# HIDdoorUnlocker.net
KiCad netlist of a schematic drawn in EAGLE
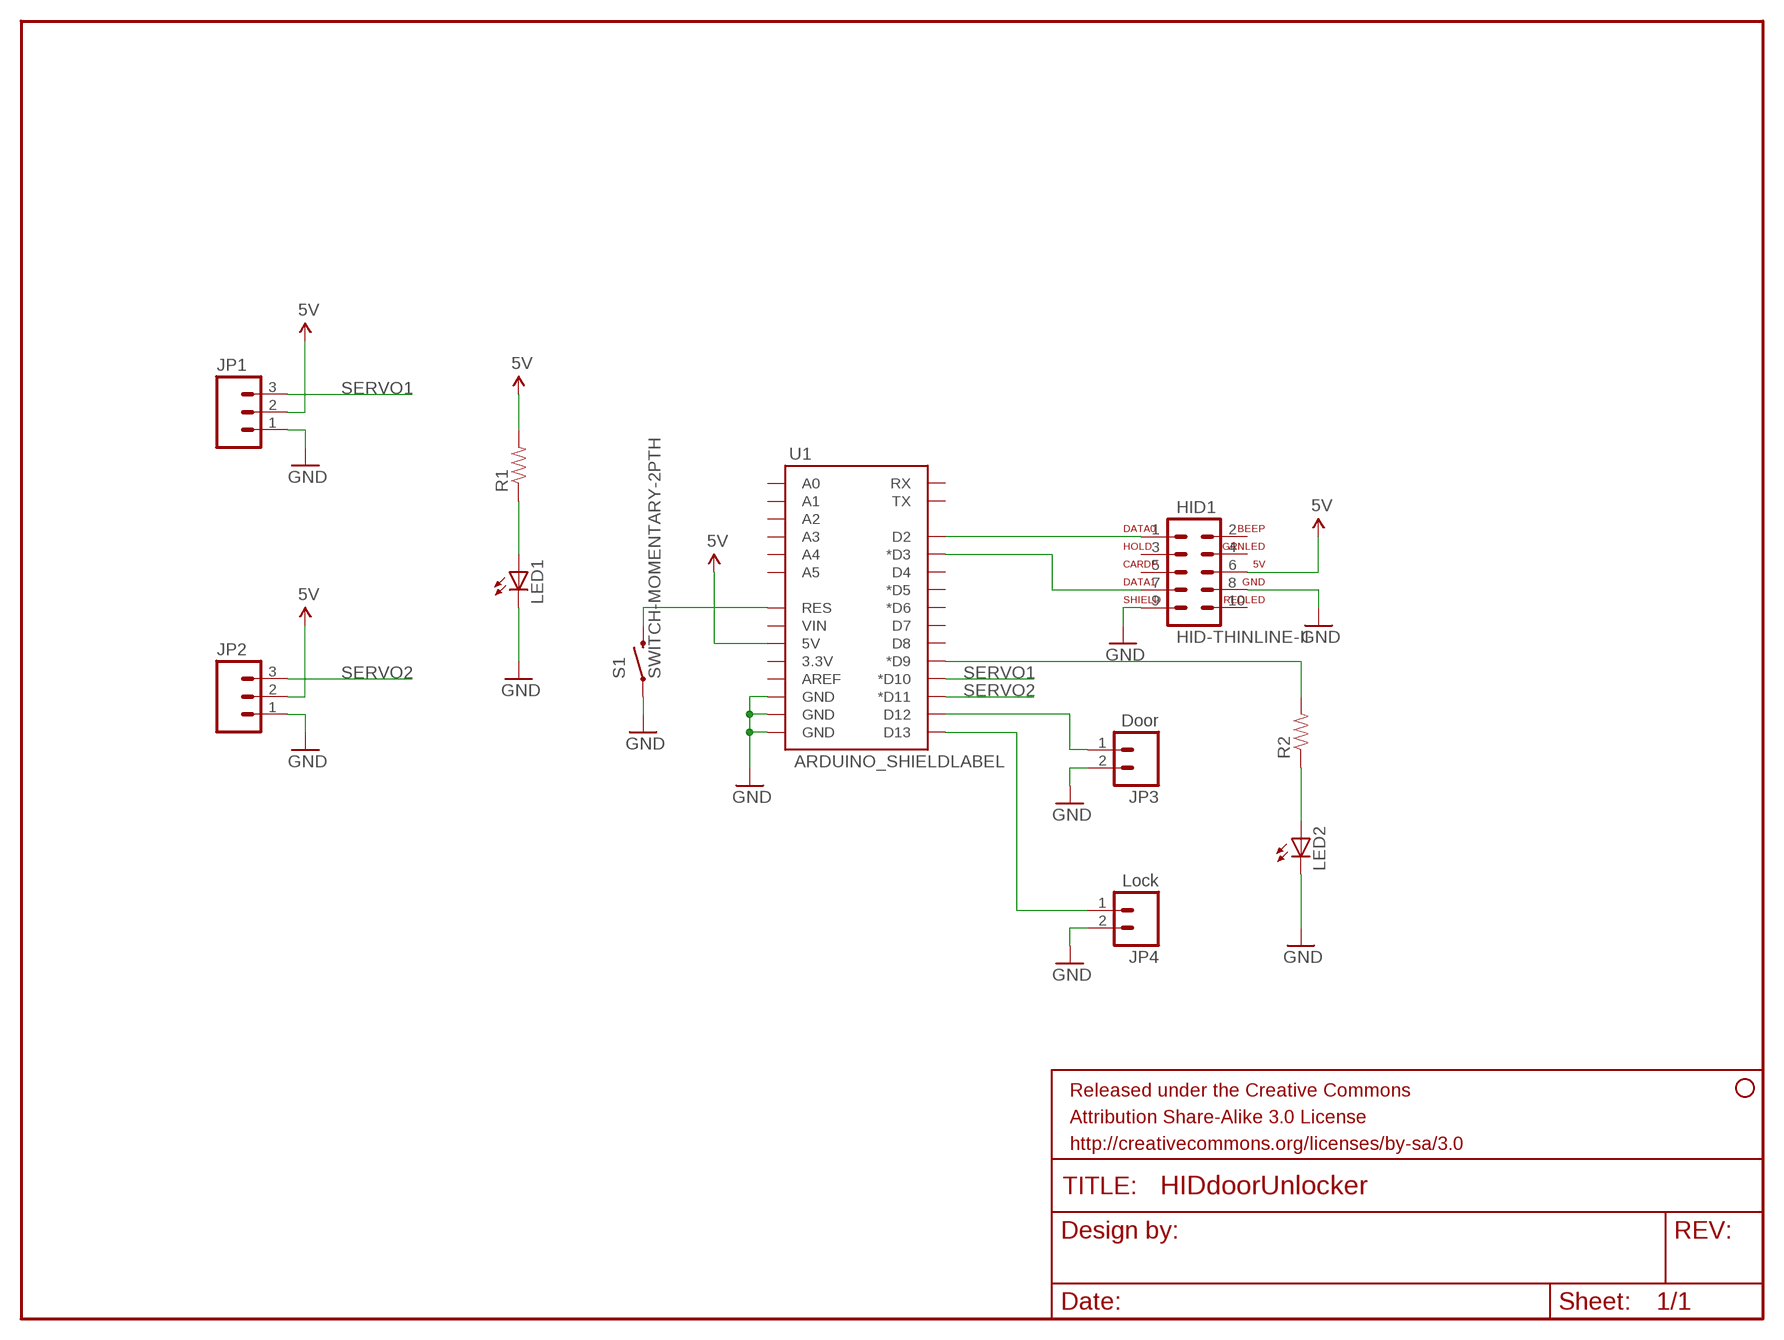
[diagram p0: schematic, sheet 1]

(export (version "E")
  (design (tool "Eeschema 10.0.6"))
  (components
    (comp (ref "FRAME1")
      (value "FRAME-LETTER")
      (footprint "eagle-import:CREATIVE_COMMONS")
      (libsource (lib "eagle-import") (part "FRAME-LETTER"))
    )
    (comp (ref "HID1")
      (value "HID-THINLINE-II")
      (footprint "eagle-import:HID-2X5")
      (libsource (lib "eagle-import") (part "HID-THINLINE-II"))
    )
    (comp (ref "JP1")
      (value "M03PTH")
      (footprint "eagle-import:1X03")
      (libsource (lib "eagle-import") (part "M03PTH"))
    )
    (comp (ref "JP2")
      (value "M03PTH")
      (footprint "eagle-import:1X03")
      (libsource (lib "eagle-import") (part "M03PTH"))
    )
    (comp (ref "JP3")
      (value "Door")
      (footprint "eagle-import:1X02")
      (libsource (lib "eagle-import") (part "M02PTH"))
    )
    (comp (ref "JP4")
      (value "Lock")
      (footprint "eagle-import:1X02")
      (libsource (lib "eagle-import") (part "M02PTH"))
    )
    (comp (ref "LED1")
      (value "LED5MM")
      (footprint "eagle-import:LED5MM")
      (libsource (lib "eagle-import") (part "LED5MM"))
    )
    (comp (ref "LED2")
      (value "LED5MM")
      (footprint "eagle-import:LED5MM")
      (libsource (lib "eagle-import") (part "LED5MM"))
    )
    (comp (ref "R1")
      (value "RESISTORPTH-1/4W")
      (footprint "eagle-import:AXIAL-0.4")
      (libsource (lib "eagle-import") (part "RESISTORPTH-1/4W"))
    )
    (comp (ref "R2")
      (value "RESISTORPTH-1/4W")
      (footprint "eagle-import:AXIAL-0.4")
      (libsource (lib "eagle-import") (part "RESISTORPTH-1/4W"))
    )
    (comp (ref "S1")
      (value "SWITCH-MOMENTARY-2PTH")
      (footprint "eagle-import:TACTILE-PTH")
      (libsource (lib "eagle-import") (part "SWITCH-MOMENTARY-2PTH"))
    )
    (comp (ref "STANDOFF1")
      (value "STAND-OFF")
      (footprint "eagle-import:STAND-OFF")
      (libsource (lib "eagle-import") (part "STAND-OFF"))
    )
    (comp (ref "U1")
      (value "ARDUINO_SHIELDLABEL")
      (footprint "eagle-import:DUEMILANOVE_SHIELD")
      (libsource (lib "eagle-import") (part "ARDUINO_SHIELDLABEL"))
    )
  )
  (nets
    (net (code "1") (name "/SERVO1") (class "Default")
      (node (ref "JP1") (pin "3") (pinfunction "3_3") (pintype "passive"))
      (node (ref "U1") (pin "D10") (pinfunction "*D10_D10") (pintype "bidirectional"))
    )
    (net (code "2") (name "/SERVO2") (class "Default")
      (node (ref "JP2") (pin "3") (pinfunction "3_3") (pintype "passive"))
      (node (ref "U1") (pin "D11") (pinfunction "*D11_D11") (pintype "bidirectional"))
    )
    (net (code "3") (name "5V") (class "Default")
      (node (ref "HID1") (pin "6") (pinfunction "6_6") (pintype "passive"))
      (node (ref "JP1") (pin "2") (pinfunction "2_2") (pintype "passive"))
      (node (ref "JP2") (pin "2") (pinfunction "2_2") (pintype "passive"))
      (node (ref "R1") (pin "P$2") (pinfunction "2_P$2") (pintype "passive"))
      (node (ref "U1") (pin "5V") (pinfunction "5V_5V") (pintype "bidirectional"))
    )
    (net (code "4") (name "GND") (class "Default")
      (node (ref "HID1") (pin "8") (pinfunction "8_8") (pintype "passive"))
      (node (ref "HID1") (pin "9") (pinfunction "9_9") (pintype "passive"))
      (node (ref "JP1") (pin "1") (pinfunction "1_1") (pintype "passive"))
      (node (ref "JP2") (pin "1") (pinfunction "1_1") (pintype "passive"))
      (node (ref "JP3") (pin "2") (pinfunction "2_2") (pintype "passive"))
      (node (ref "JP4") (pin "2") (pinfunction "2_2") (pintype "passive"))
      (node (ref "LED1") (pin "K") (pinfunction "C_K") (pintype "passive"))
      (node (ref "LED2") (pin "K") (pinfunction "C_K") (pintype "passive"))
      (node (ref "S1") (pin "1") (pinfunction "1_1") (pintype "passive"))
      (node (ref "U1") (pin "GND@0") (pinfunction "GND_GND@0") (pintype "bidirectional"))
      (node (ref "U1") (pin "GND@1") (pinfunction "GND_GND@1") (pintype "bidirectional"))
      (node (ref "U1") (pin "GND@2") (pinfunction "GND_GND@2") (pintype "bidirectional"))
    )
    (net (code "5") (name "Net-(HID1-Pad1)") (class "Default")
      (node (ref "HID1") (pin "1") (pinfunction "1_1") (pintype "passive"))
      (node (ref "U1") (pin "D2") (pinfunction "D2_D2") (pintype "bidirectional"))
    )
    (net (code "6") (name "Net-(JP3-Pad1)") (class "Default")
      (node (ref "JP3") (pin "1") (pinfunction "1_1") (pintype "passive"))
      (node (ref "U1") (pin "D12") (pinfunction "D12_D12") (pintype "bidirectional"))
    )
    (net (code "7") (name "Net-(JP4-Pad1)") (class "Default")
      (node (ref "JP4") (pin "1") (pinfunction "1_1") (pintype "passive"))
      (node (ref "U1") (pin "D13") (pinfunction "D13_D13") (pintype "bidirectional"))
    )
    (net (code "8") (name "Net-(R1-1)") (class "Default")
      (node (ref "LED1") (pin "A") (pinfunction "A_A") (pintype "passive"))
      (node (ref "R1") (pin "P$1") (pinfunction "1_P$1") (pintype "passive"))
    )
    (net (code "9") (name "Net-(R2-1)") (class "Default")
      (node (ref "LED2") (pin "A") (pinfunction "A_A") (pintype "passive"))
      (node (ref "R2") (pin "P$1") (pinfunction "1_P$1") (pintype "passive"))
    )
    (net (code "10") (name "Net-(R2-2)") (class "Default")
      (node (ref "R2") (pin "P$2") (pinfunction "2_P$2") (pintype "passive"))
      (node (ref "U1") (pin "D9") (pinfunction "*D9_D9") (pintype "bidirectional"))
    )
    (net (code "11") (name "Net-(S1-2)") (class "Default")
      (node (ref "S1") (pin "3") (pinfunction "2_3") (pintype "passive"))
      (node (ref "U1") (pin "RES") (pinfunction "RES_RES") (pintype "bidirectional"))
    )
    (net (code "12") (name "Net-(U1-*D3)") (class "Default")
      (node (ref "HID1") (pin "7") (pinfunction "7_7") (pintype "passive"))
      (node (ref "U1") (pin "D3") (pinfunction "*D3_D3") (pintype "bidirectional"))
    )
    (net (code "13") (name "unconnected-(HID1-Pad2)") (class "Default")
      (node (ref "HID1") (pin "2") (pinfunction "2_2") (pintype "passive"))
    )
    (net (code "14") (name "unconnected-(HID1-Pad3)") (class "Default")
      (node (ref "HID1") (pin "3") (pinfunction "3_3") (pintype "passive"))
    )
    (net (code "15") (name "unconnected-(HID1-Pad4)") (class "Default")
      (node (ref "HID1") (pin "4") (pinfunction "4_4") (pintype "passive"))
    )
    (net (code "16") (name "unconnected-(HID1-Pad5)") (class "Default")
      (node (ref "HID1") (pin "5") (pinfunction "5_5") (pintype "passive"))
    )
    (net (code "17") (name "unconnected-(HID1-Pad10)") (class "Default")
      (node (ref "HID1") (pin "10") (pinfunction "10_10") (pintype "passive"))
    )
    (net (code "18") (name "unconnected-(U1-*D5-PadD5)") (class "Default")
      (node (ref "U1") (pin "D5") (pinfunction "*D5_D5") (pintype "bidirectional"))
    )
    (net (code "19") (name "unconnected-(U1-*D6-PadD6)") (class "Default")
      (node (ref "U1") (pin "D6") (pinfunction "*D6_D6") (pintype "bidirectional"))
    )
    (net (code "20") (name "unconnected-(U1-Pad3.3V)") (class "Default")
      (node (ref "U1") (pin "3.3V") (pinfunction "3.3V_3.3V") (pintype "bidirectional"))
    )
    (net (code "21") (name "unconnected-(U1-PadA0)") (class "Default")
      (node (ref "U1") (pin "A0") (pinfunction "A0_A0") (pintype "bidirectional"))
    )
    (net (code "22") (name "unconnected-(U1-PadA1)") (class "Default")
      (node (ref "U1") (pin "A1") (pinfunction "A1_A1") (pintype "bidirectional"))
    )
    (net (code "23") (name "unconnected-(U1-PadA2)") (class "Default")
      (node (ref "U1") (pin "A2") (pinfunction "A2_A2") (pintype "bidirectional"))
    )
    (net (code "24") (name "unconnected-(U1-PadA3)") (class "Default")
      (node (ref "U1") (pin "A3") (pinfunction "A3_A3") (pintype "bidirectional"))
    )
    (net (code "25") (name "unconnected-(U1-PadA4)") (class "Default")
      (node (ref "U1") (pin "A4") (pinfunction "A4_A4") (pintype "bidirectional"))
    )
    (net (code "26") (name "unconnected-(U1-PadA5)") (class "Default")
      (node (ref "U1") (pin "A5") (pinfunction "A5_A5") (pintype "bidirectional"))
    )
    (net (code "27") (name "unconnected-(U1-PadAREF)") (class "Default")
      (node (ref "U1") (pin "AREF") (pinfunction "AREF_AREF") (pintype "bidirectional"))
    )
    (net (code "28") (name "unconnected-(U1-PadD4)") (class "Default")
      (node (ref "U1") (pin "D4") (pinfunction "D4_D4") (pintype "bidirectional"))
    )
    (net (code "29") (name "unconnected-(U1-PadD7)") (class "Default")
      (node (ref "U1") (pin "D7") (pinfunction "D7_D7") (pintype "bidirectional"))
    )
    (net (code "30") (name "unconnected-(U1-PadD8)") (class "Default")
      (node (ref "U1") (pin "D8") (pinfunction "D8_D8") (pintype "bidirectional"))
    )
    (net (code "31") (name "unconnected-(U1-PadRX)") (class "Default")
      (node (ref "U1") (pin "RX") (pinfunction "RX_RX") (pintype "bidirectional"))
    )
    (net (code "32") (name "unconnected-(U1-PadTX)") (class "Default")
      (node (ref "U1") (pin "TX") (pinfunction "TX_TX") (pintype "bidirectional"))
    )
    (net (code "33") (name "unconnected-(U1-PadVIN)") (class "Default")
      (node (ref "U1") (pin "VIN") (pinfunction "VIN_VIN") (pintype "bidirectional"))
    )
  )
)
